# SV601272A-DAC.net
KiCad netlist of a schematic drawn in Altium Designer
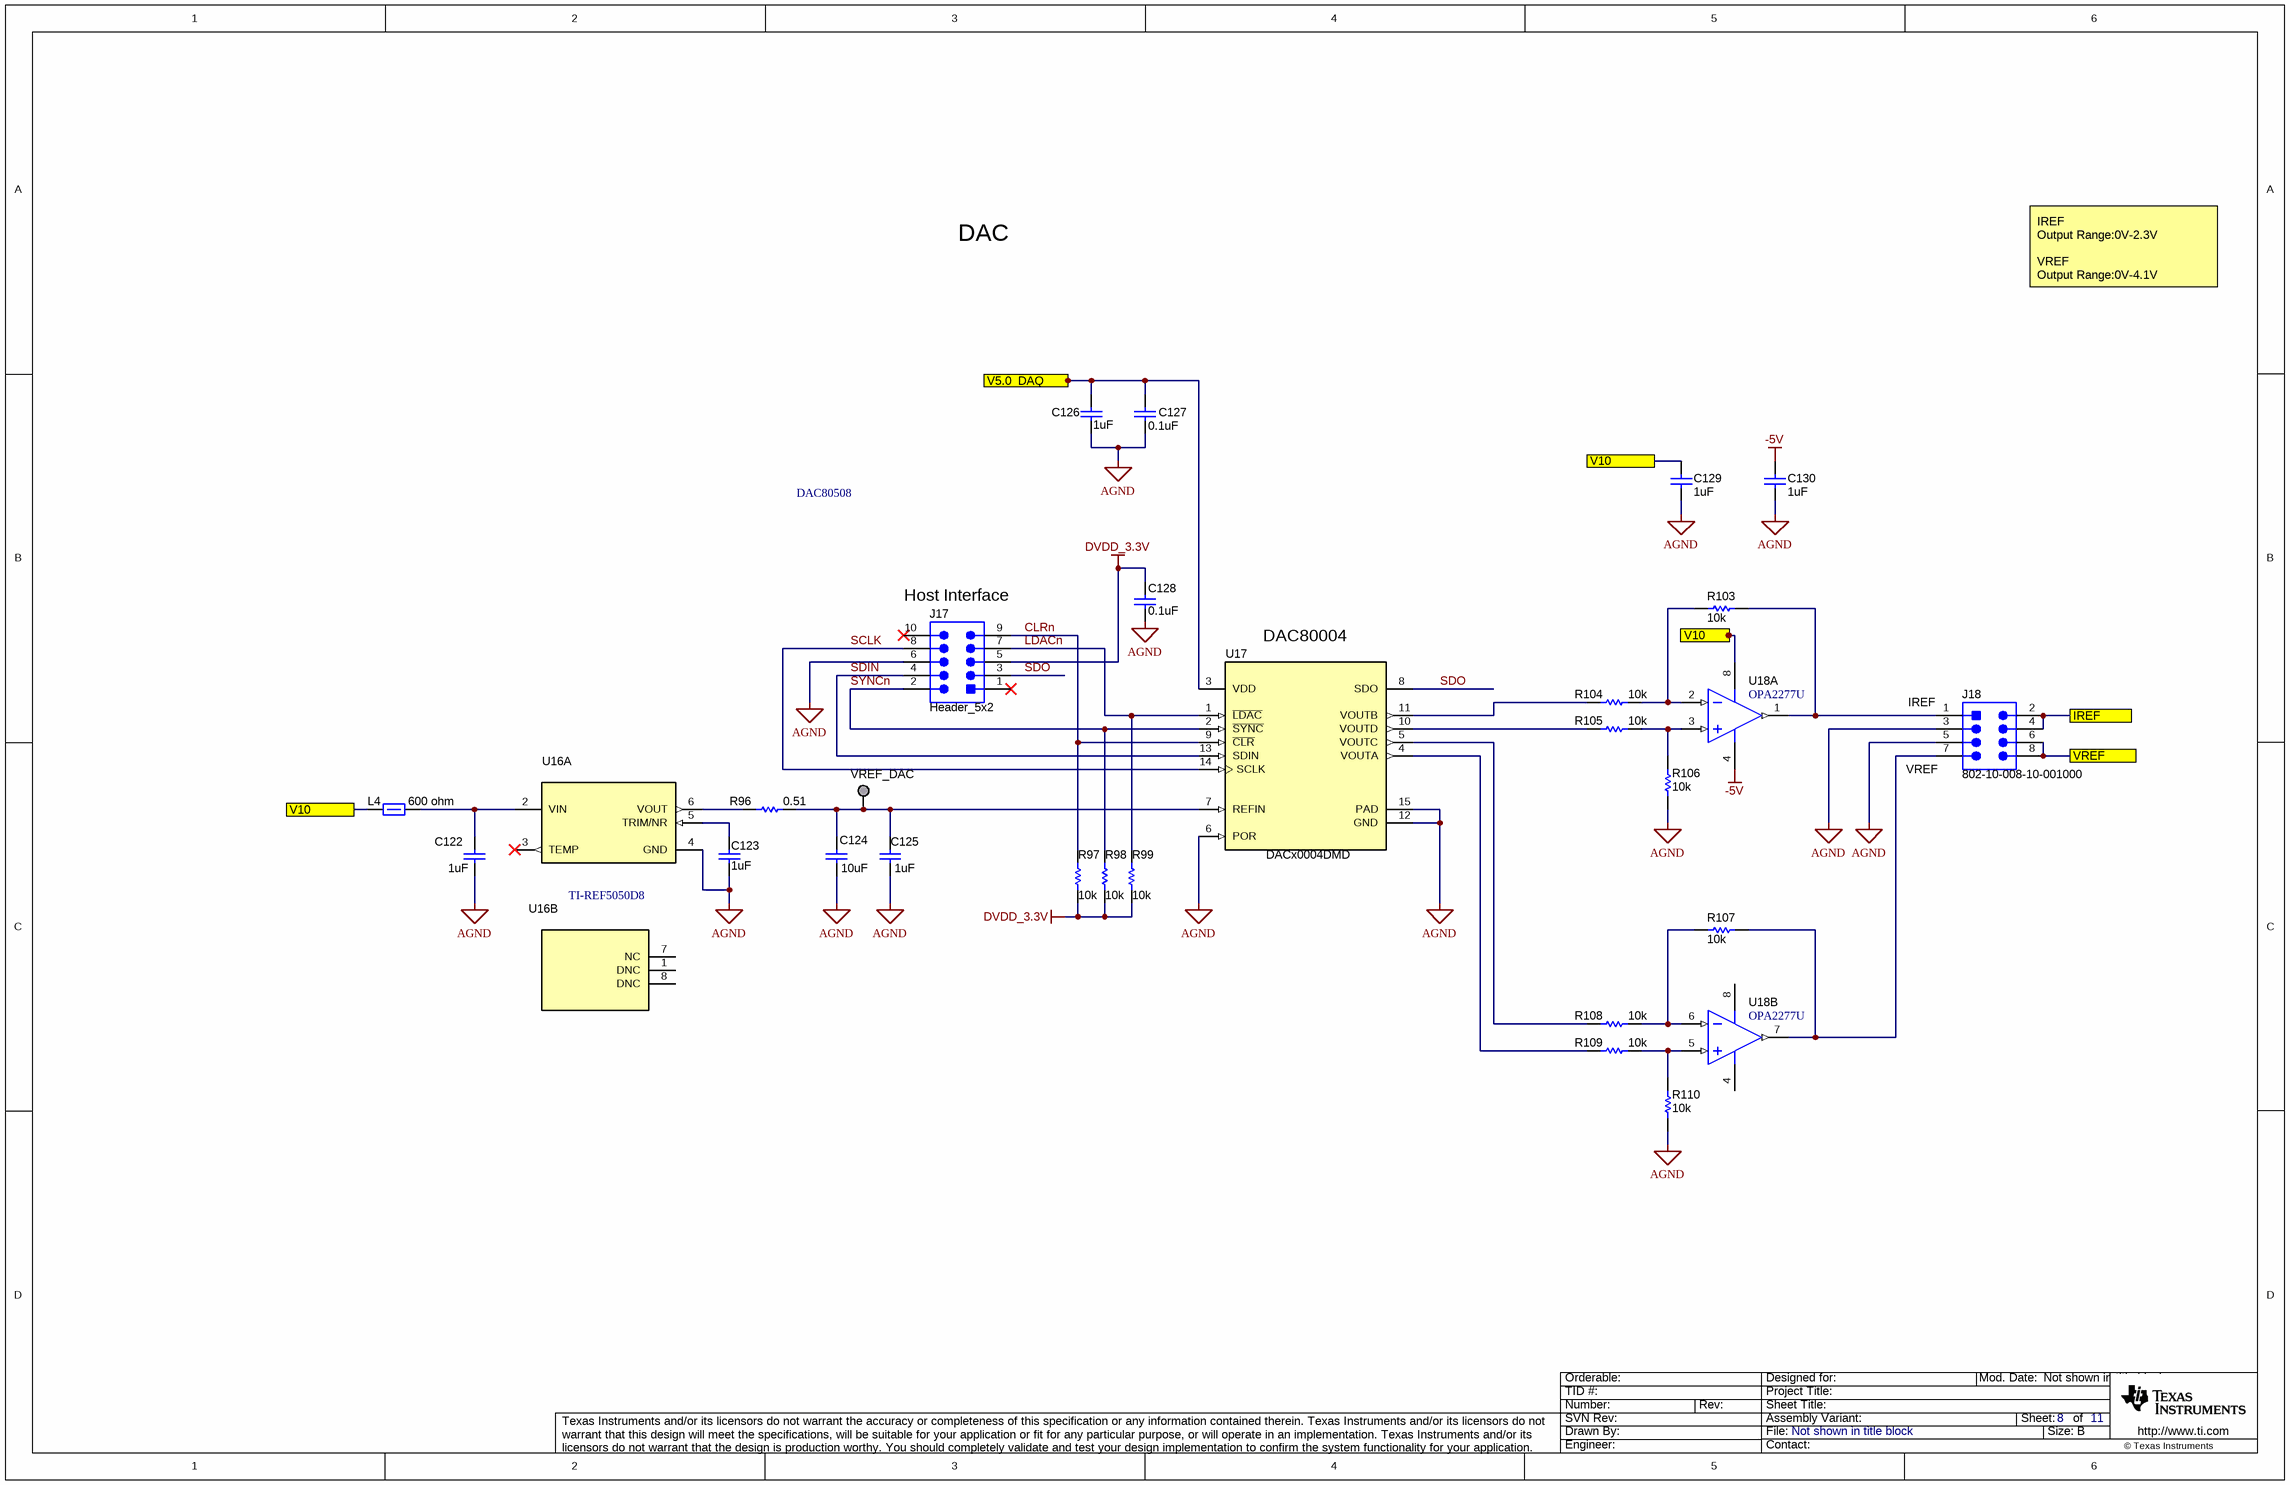
[diagram p0: SV601272A-DAC.SchDoc]

(export (version "E")
  (design (tool "Eeschema 10.0.6"))
  (components
    (comp (ref "C122")
      (value "Capacitor")
      (footprint "1206")
      (description "CAP, CERM, 1 uF, 25 V, +/- 10%, X7R, 1206")
      (fields
        (field (name "PARTNUMBER") "12063C105KAT2A")
        (field (name "VALUEDISPLAYED") "1uF")
        (field (name "MANUFACTURER") "AVX")
        (field (name "PUBLISHER") "Texas Instruments")
      )
      (libsource (lib "Altium Vault - TI") (part "CMP-0008509-2"))
    )
    (comp (ref "C123")
      (value "Capacitor")
      (footprint "1206")
      (description "CAP, CERM, 1 uF, 25 V, +/- 10%, X7R, 1206")
      (fields
        (field (name "PARTNUMBER") "12063C105KAT2A")
        (field (name "VALUEDISPLAYED") "1uF")
        (field (name "MANUFACTURER") "AVX")
        (field (name "PUBLISHER") "Texas Instruments")
      )
      (libsource (lib "Altium Vault - TI") (part "CMP-0008509-2"))
    )
    (comp (ref "C124")
      (value "Capacitor")
      (footprint "0805_HV")
      (description "CAP, CERM, 10 uF, 35 V, +/- 10%, X6S, 0805")
      (fields
        (field (name "PARTNUMBER") "GRM21BC8YA106KE11L")
        (field (name "VALUEDISPLAYED") "10uF")
        (field (name "MANUFACTURER") "MuRata")
        (field (name "PUBLISHER") "Texas Instruments")
      )
      (libsource (lib "Altium Vault - TI") (part "CMP-0008273-1"))
    )
    (comp (ref "C125")
      (value "Capacitor")
      (footprint "1206")
      (description "CAP, CERM, 1 uF, 25 V, +/- 10%, X7R, 1206")
      (fields
        (field (name "PARTNUMBER") "12063C105KAT2A")
        (field (name "VALUEDISPLAYED") "1uF")
        (field (name "MANUFACTURER") "AVX")
        (field (name "PUBLISHER") "Texas Instruments")
      )
      (libsource (lib "Altium Vault - TI") (part "CMP-0008509-2"))
    )
    (comp (ref "C126")
      (value "Capacitor")
      (footprint "1206")
      (description "CAP, CERM, 1 uF, 25 V, +/- 10%, X7R, 1206")
      (fields
        (field (name "PARTNUMBER") "12063C105KAT2A")
        (field (name "VALUEDISPLAYED") "1uF")
        (field (name "MANUFACTURER") "AVX")
        (field (name "PUBLISHER") "Texas Instruments")
      )
      (libsource (lib "Altium Vault - TI") (part "CMP-0008509-2"))
    )
    (comp (ref "C127")
      (value "Capacitor")
      (footprint "0603")
      (description "CAP, CERM, 0.1 uF, 16 V, +/- 5%, X7R, 0603")
      (fields
        (field (name "PARTNUMBER") "C0603C104J4RACTU")
        (field (name "VALUEDISPLAYED") "0.1uF")
        (field (name "MANUFACTURER") "Kemet")
        (field (name "PUBLISHER") "Texas Instruments")
      )
      (libsource (lib "Altium Vault - TI") (part "CMP-0006857-4"))
    )
    (comp (ref "C128")
      (value "Capacitor")
      (footprint "0603")
      (description "CAP, CERM, 0.1 uF, 16 V, +/- 5%, X7R, 0603")
      (fields
        (field (name "PARTNUMBER") "C0603C104J4RACTU")
        (field (name "VALUEDISPLAYED") "0.1uF")
        (field (name "MANUFACTURER") "Kemet")
        (field (name "PUBLISHER") "Texas Instruments")
      )
      (libsource (lib "Altium Vault - TI") (part "CMP-0006857-4"))
    )
    (comp (ref "C129")
      (value "Capacitor")
      (footprint "0603")
      (description "CAP, CERM, 1 uF, 35 V, +/- 10%, X7R, AEC-Q200 Grade 1, 0603")
      (fields
        (field (name "PARTNUMBER") "CGA3E1X7R1V105K080AC")
        (field (name "VALUEDISPLAYED") "1uF")
        (field (name "MANUFACTURER") "TDK")
        (field (name "PUBLISHER") "Texas Instruments")
      )
      (libsource (lib "Altium Vault - TI") (part "CMP-0007067-4"))
    )
    (comp (ref "C130")
      (value "Capacitor")
      (footprint "0603")
      (description "CAP, CERM, 1 uF, 35 V, +/- 10%, X7R, AEC-Q200 Grade 1, 0603")
      (fields
        (field (name "PARTNUMBER") "CGA3E1X7R1V105K080AC")
        (field (name "VALUEDISPLAYED") "1uF")
        (field (name "MANUFACTURER") "TDK")
        (field (name "PUBLISHER") "Texas Instruments")
      )
      (libsource (lib "Altium Vault - TI") (part "CMP-0007067-4"))
    )
    (comp (ref "J17")
      (value "Header_5x2")
      (footprint "Assman_AWHW-10G-0x02-T")
      (description "Header(Shrouded), 2.54mm, 5x2, Gold, TH")
      (fields
        (field (name "PARTNUMBER") "AWHW-10G-0202-T")
        (field (name "MANUFACTURER") "Assman WSW")
        (field (name "PUBLISHER") "Texas Instruments")
      )
      (libsource (lib "Altium Vault - TI") (part "CMP-0075161-1"))
    )
    (comp (ref "J18")
      (value "802-10-008-10-001000")
      (footprint "Mill-Max_802-10-008-10-001000")
      (description "Header, 2.54 mm, 4x2, Gold, TH")
      (fields (field (name "MANUFACTURER") "Mill-Max") (field (name "PUBLISHER") "Texas Instruments"))
      (libsource (lib "Altium Vault - TI") (part "CMP-0055096-1"))
    )
    (comp (ref "L4")
      (value "600 ohm")
      (footprint "0603")
      (description "Ferrite Bead, 600 ohm @ 100 MHz, 1 A, 0603")
      (fields
        (field (name "PARTNUMBER") "742792651")
        (field (name "MANUFACTURER") "Wurth Elektronik")
        (field (name "PUBLISHER") "Texas Instruments")
      )
      (libsource (lib "Altium Vault - TI") (part "Ferrite_Bead"))
    )
    (comp (ref "R96")
      (value "Resistor")
      (footprint "0603")
      (description "RES, 0.51, 1%, 0.1 W, AEC-Q200 Grade 1, 0603")
      (fields
        (field (name "PARTNUMBER") "ERJ-3RQFR51V")
        (field (name "VALUEDISPLAYED") "0.51")
        (field (name "MANUFACTURER") "Panasonic")
        (field (name "PUBLISHER") "Texas Instruments")
      )
      (libsource (lib "Altium Vault - TI") (part "CMP-0022717-2"))
    )
    (comp (ref "R97")
      (value "Resistor")
      (footprint "0603")
      (description "RES, 10 k, 5%, 0.1 W, AEC-Q200 Grade 0, 0603")
      (fields
        (field (name "PARTNUMBER") "CRCW060310K0JNEA")
        (field (name "VALUEDISPLAYED") "10k")
        (field (name "MANUFACTURER") "Vishay-Dale")
      )
      (libsource (lib "Altium Vault - TI") (part "CMP-0025701-4"))
    )
    (comp (ref "R98")
      (value "Resistor")
      (footprint "0603")
      (description "RES, 10 k, 5%, 0.1 W, AEC-Q200 Grade 0, 0603")
      (fields
        (field (name "PARTNUMBER") "CRCW060310K0JNEA")
        (field (name "VALUEDISPLAYED") "10k")
        (field (name "MANUFACTURER") "Vishay-Dale")
      )
      (libsource (lib "Altium Vault - TI") (part "CMP-0025701-4"))
    )
    (comp (ref "R99")
      (value "Resistor")
      (footprint "0603")
      (description "RES, 10 k, 5%, 0.1 W, AEC-Q200 Grade 0, 0603")
      (fields
        (field (name "PARTNUMBER") "CRCW060310K0JNEA")
        (field (name "VALUEDISPLAYED") "10k")
        (field (name "MANUFACTURER") "Vishay-Dale")
      )
      (libsource (lib "Altium Vault - TI") (part "CMP-0025701-4"))
    )
    (comp (ref "R103")
      (value "Resistor")
      (footprint "0603")
      (description "RES, 10 k, 5%, 0.1 W, AEC-Q200 Grade 0, 0603")
      (fields
        (field (name "PARTNUMBER") "CRCW060310K0JNEA")
        (field (name "VALUEDISPLAYED") "10k")
        (field (name "MANUFACTURER") "Vishay-Dale")
      )
      (libsource (lib "Altium Vault - TI") (part "CMP-0025701-4"))
    )
    (comp (ref "R104")
      (value "Resistor")
      (footprint "0603")
      (description "RES, 10 k, 5%, 0.1 W, AEC-Q200 Grade 0, 0603")
      (fields
        (field (name "PARTNUMBER") "CRCW060310K0JNEA")
        (field (name "VALUEDISPLAYED") "10k")
        (field (name "MANUFACTURER") "Vishay-Dale")
      )
      (libsource (lib "Altium Vault - TI") (part "CMP-0025701-4"))
    )
    (comp (ref "R105")
      (value "Resistor")
      (footprint "0603")
      (description "RES, 10 k, 5%, 0.1 W, AEC-Q200 Grade 0, 0603")
      (fields
        (field (name "PARTNUMBER") "CRCW060310K0JNEA")
        (field (name "VALUEDISPLAYED") "10k")
        (field (name "MANUFACTURER") "Vishay-Dale")
      )
      (libsource (lib "Altium Vault - TI") (part "CMP-0025701-4"))
    )
    (comp (ref "R106")
      (value "Resistor")
      (footprint "0603")
      (description "RES, 10 k, 5%, 0.1 W, AEC-Q200 Grade 0, 0603")
      (fields
        (field (name "PARTNUMBER") "CRCW060310K0JNEA")
        (field (name "VALUEDISPLAYED") "10k")
        (field (name "MANUFACTURER") "Vishay-Dale")
      )
      (libsource (lib "Altium Vault - TI") (part "CMP-0025701-4"))
    )
    (comp (ref "R107")
      (value "Resistor")
      (footprint "0603")
      (description "RES, 10 k, 5%, 0.1 W, AEC-Q200 Grade 0, 0603")
      (fields
        (field (name "PARTNUMBER") "CRCW060310K0JNEA")
        (field (name "VALUEDISPLAYED") "10k")
        (field (name "MANUFACTURER") "Vishay-Dale")
      )
      (libsource (lib "Altium Vault - TI") (part "CMP-0025701-4"))
    )
    (comp (ref "R108")
      (value "Resistor")
      (footprint "0603")
      (description "RES, 10 k, 5%, 0.1 W, AEC-Q200 Grade 0, 0603")
      (fields
        (field (name "PARTNUMBER") "CRCW060310K0JNEA")
        (field (name "VALUEDISPLAYED") "10k")
        (field (name "MANUFACTURER") "Vishay-Dale")
      )
      (libsource (lib "Altium Vault - TI") (part "CMP-0025701-4"))
    )
    (comp (ref "R109")
      (value "Resistor")
      (footprint "0603")
      (description "RES, 10 k, 5%, 0.1 W, AEC-Q200 Grade 0, 0603")
      (fields
        (field (name "PARTNUMBER") "CRCW060310K0JNEA")
        (field (name "VALUEDISPLAYED") "10k")
        (field (name "MANUFACTURER") "Vishay-Dale")
      )
      (libsource (lib "Altium Vault - TI") (part "CMP-0025701-4"))
    )
    (comp (ref "R110")
      (value "Resistor")
      (footprint "0603")
      (description "RES, 10 k, 5%, 0.1 W, AEC-Q200 Grade 0, 0603")
      (fields
        (field (name "PARTNUMBER") "CRCW060310K0JNEA")
        (field (name "VALUEDISPLAYED") "10k")
        (field (name "MANUFACTURER") "Vishay-Dale")
      )
      (libsource (lib "Altium Vault - TI") (part "CMP-0025701-4"))
    )
    (comp (ref "U16")
      (value "TI-REF5050D8")
      (footprint "D0008A_N")
      (fields (field (name "PARTNUMBER") "REF5050AID") (field (name "MANUFACTURER") "Texas Instruments"))
      (libsource (lib "Altium Vault - TI") (part "CMP-0032617-1"))
    )
    (comp (ref "U17")
      (value "DACx0004DMD")
      (footprint "DMD0014A")
      (description "QUAD 16-BIT, 1LSB INL, BUFFERED, VOLTAGE-OUTPUT DIGITAL-to-ANALOG CONVERTERS, DMD0014A (VSON-14)")
      (fields
        (field (name "PARTNUMBER") "DAC80004IDMD")
        (field (name "MANUFACTURER") "Texas Instruments")
        (field (name "PUBLISHER") "Texas Instruments")
      )
      (libsource (lib "Altium Vault - TI") (part "DACx0004DMD"))
    )
    (comp (ref "U18")
      (value "OPA2277U")
      (footprint "D0008A_N")
      (fields (field (name "MANUFACTURER") "Texas Instruments"))
      (libsource (lib "Altium Vault - TI") (part "CMP-0040655-1"))
    )
    (comp (ref "VREF_DAC")
      (value "Pogo Pad")
      (footprint "PogoPad")
      (description "Pad for Pogo Pin Connector")
      (fields (field (name "SYMBOLCREATOR") "codlsc") (field (name "PUBLISHER") "Texas Instruments"))
      (libsource (lib "MiscParts") (part "PogoPad"))
    )
  )
  (nets
    (net (code "1") (name "-5V") (class "Default")
      (node (ref "C130") (pin "1") (pinfunction "1_1") (pintype "passive"))
      (node (ref "U18") (pin "4") (pinfunction "V-_4") (pintype "power_in"))
    )
    (net (code "2") (name "/CLRn") (class "Default")
      (node (ref "J17") (pin "9") (pinfunction "9_9") (pintype "passive"))
      (node (ref "R97") (pin "2") (pinfunction "2_2") (pintype "passive"))
      (node (ref "U17") (pin "9") (pinfunction "CLR_9") (pintype "input"))
    )
    (net (code "3") (name "/IREF") (class "Default")
      (node (ref "J18") (pin "2") (pinfunction "2_2") (pintype "passive"))
      (node (ref "J18") (pin "4") (pinfunction "4_4") (pintype "passive"))
    )
    (net (code "4") (name "/LDACn") (class "Default")
      (node (ref "J17") (pin "7") (pinfunction "7_7") (pintype "passive"))
      (node (ref "R99") (pin "2") (pinfunction "2_2") (pintype "passive"))
      (node (ref "U17") (pin "1") (pinfunction "LDAC_1") (pintype "input"))
    )
    (net (code "5") (name "/SCLK") (class "Default")
      (node (ref "J17") (pin "8") (pinfunction "8_8") (pintype "passive"))
      (node (ref "U17") (pin "14") (pinfunction "SCLK_14") (pintype "input"))
    )
    (net (code "6") (name "/SDIN") (class "Default")
      (node (ref "J17") (pin "4") (pinfunction "4_4") (pintype "passive"))
      (node (ref "U17") (pin "13") (pinfunction "SDIN_13") (pintype "input"))
    )
    (net (code "7") (name "/SDO") (class "Default")
      (node (ref "J17") (pin "3") (pinfunction "3_3") (pintype "passive"))
      (node (ref "U17") (pin "8") (pinfunction "SDO_8") (pintype "tri_state"))
    )
    (net (code "8") (name "/SYNCn") (class "Default")
      (node (ref "J17") (pin "2") (pinfunction "2_2") (pintype "passive"))
      (node (ref "R98") (pin "2") (pinfunction "2_2") (pintype "passive"))
      (node (ref "U17") (pin "2") (pinfunction "SYNC_2") (pintype "input"))
    )
    (net (code "9") (name "/V5.0_DAQ") (class "Default")
      (node (ref "C126") (pin "1") (pinfunction "1_1") (pintype "passive"))
      (node (ref "C127") (pin "1") (pinfunction "1_1") (pintype "passive"))
      (node (ref "U17") (pin "3") (pinfunction "VDD_3") (pintype "power_in"))
    )
    (net (code "10") (name "/V10") (class "Default")
      (node (ref "C129") (pin "1") (pinfunction "1_1") (pintype "passive"))
      (node (ref "L4") (pin "1") (pinfunction "1_1") (pintype "passive"))
      (node (ref "U18") (pin "8") (pinfunction "V+_8") (pintype "power_in"))
    )
    (net (code "11") (name "/VREF") (class "Default")
      (node (ref "J18") (pin "6") (pinfunction "6_6") (pintype "passive"))
      (node (ref "J18") (pin "8") (pinfunction "8_8") (pintype "passive"))
    )
    (net (code "12") (name "AGND") (class "Default")
      (node (ref "C122") (pin "2") (pinfunction "2_2") (pintype "passive"))
      (node (ref "C123") (pin "2") (pinfunction "2_2") (pintype "passive"))
      (node (ref "C124") (pin "2") (pinfunction "2_2") (pintype "passive"))
      (node (ref "C125") (pin "2") (pinfunction "2_2") (pintype "passive"))
      (node (ref "C126") (pin "2") (pinfunction "2_2") (pintype "passive"))
      (node (ref "C127") (pin "2") (pinfunction "2_2") (pintype "passive"))
      (node (ref "C128") (pin "2") (pinfunction "2_2") (pintype "passive"))
      (node (ref "C129") (pin "2") (pinfunction "2_2") (pintype "passive"))
      (node (ref "C130") (pin "2") (pinfunction "2_2") (pintype "passive"))
      (node (ref "J17") (pin "6") (pinfunction "6_6") (pintype "passive"))
      (node (ref "J18") (pin "3") (pinfunction "3_3") (pintype "passive"))
      (node (ref "J18") (pin "5") (pinfunction "5_5") (pintype "passive"))
      (node (ref "R106") (pin "1") (pinfunction "1_1") (pintype "passive"))
      (node (ref "R110") (pin "1") (pinfunction "1_1") (pintype "passive"))
      (node (ref "U16") (pin "4") (pinfunction "GND_4") (pintype "power_in"))
      (node (ref "U17") (pin "12") (pinfunction "GND_12") (pintype "power_in"))
      (node (ref "U17") (pin "15") (pinfunction "PAD_15") (pintype "passive"))
      (node (ref "U17") (pin "6") (pinfunction "POR_6") (pintype "input"))
    )
    (net (code "13") (name "DVDD_3.3V") (class "Default")
      (node (ref "C128") (pin "1") (pinfunction "1_1") (pintype "passive"))
      (node (ref "J17") (pin "5") (pinfunction "5_5") (pintype "passive"))
      (node (ref "R97") (pin "1") (pinfunction "1_1") (pintype "passive"))
      (node (ref "R98") (pin "1") (pinfunction "1_1") (pintype "passive"))
      (node (ref "R99") (pin "1") (pinfunction "1_1") (pintype "passive"))
    )
    (net (code "14") (name "Net-(U16A-TRIM{slash}NR)") (class "Default")
      (node (ref "C123") (pin "1") (pinfunction "1_1") (pintype "passive"))
      (node (ref "U16") (pin "5") (pinfunction "TRIM/NR_5") (pintype "input"))
    )
    (net (code "15") (name "Net-(U16A-VIN)") (class "Default")
      (node (ref "C122") (pin "1") (pinfunction "1_1") (pintype "passive"))
      (node (ref "L4") (pin "2") (pinfunction "2_2") (pintype "passive"))
      (node (ref "U16") (pin "2") (pinfunction "VIN_2") (pintype "power_in"))
    )
    (net (code "16") (name "Net-(U16A-VOUT)") (class "Default")
      (node (ref "R96") (pin "1") (pinfunction "1_1") (pintype "passive"))
      (node (ref "U16") (pin "6") (pinfunction "VOUT_6") (pintype "output"))
    )
    (net (code "17") (name "Net-(U17-REFIN)") (class "Default")
      (node (ref "C124") (pin "1") (pinfunction "1_1") (pintype "passive"))
      (node (ref "C125") (pin "1") (pinfunction "1_1") (pintype "passive"))
      (node (ref "R96") (pin "2") (pinfunction "2_2") (pintype "passive"))
      (node (ref "U17") (pin "7") (pinfunction "REFIN_7") (pintype "input"))
      (node (ref "VREF_DAC") (pin "1") (pintype "passive"))
    )
    (net (code "18") (name "Net-(U17-VOUTA)") (class "Default")
      (node (ref "R109") (pin "2") (pinfunction "2_2") (pintype "passive"))
      (node (ref "U17") (pin "4") (pinfunction "VOUTA_4") (pintype "output"))
    )
    (net (code "19") (name "Net-(U17-VOUTB)") (class "Default")
      (node (ref "R104") (pin "2") (pinfunction "2_2") (pintype "passive"))
      (node (ref "U17") (pin "11") (pinfunction "VOUTB_11") (pintype "output"))
    )
    (net (code "20") (name "Net-(U17-VOUTC)") (class "Default")
      (node (ref "R108") (pin "2") (pinfunction "2_2") (pintype "passive"))
      (node (ref "U17") (pin "5") (pinfunction "VOUTC_5") (pintype "output"))
    )
    (net (code "21") (name "Net-(U17-VOUTD)") (class "Default")
      (node (ref "R105") (pin "2") (pinfunction "2_2") (pintype "passive"))
      (node (ref "U17") (pin "10") (pinfunction "VOUTD_10") (pintype "output"))
    )
    (net (code "22") (name "Net-(U18A-IN_A+)") (class "Default")
      (node (ref "R105") (pin "1") (pinfunction "1_1") (pintype "passive"))
      (node (ref "R106") (pin "2") (pinfunction "2_2") (pintype "passive"))
      (node (ref "U18") (pin "3") (pinfunction "IN_A+_3") (pintype "input"))
    )
    (net (code "23") (name "Net-(U18A-IN_A-)") (class "Default")
      (node (ref "R103") (pin "2") (pinfunction "2_2") (pintype "passive"))
      (node (ref "R104") (pin "1") (pinfunction "1_1") (pintype "passive"))
      (node (ref "U18") (pin "2") (pinfunction "IN_A-_2") (pintype "input"))
    )
    (net (code "24") (name "Net-(U18A-OUT_A)") (class "Default")
      (node (ref "J18") (pin "1") (pinfunction "1_1") (pintype "passive"))
      (node (ref "R103") (pin "1") (pinfunction "1_1") (pintype "passive"))
      (node (ref "U18") (pin "1") (pinfunction "OUT_A_1") (pintype "output"))
    )
    (net (code "25") (name "Net-(U18B-IN_B+)") (class "Default")
      (node (ref "R109") (pin "1") (pinfunction "1_1") (pintype "passive"))
      (node (ref "R110") (pin "2") (pinfunction "2_2") (pintype "passive"))
      (node (ref "U18") (pin "5") (pinfunction "IN_B+_5") (pintype "input"))
    )
    (net (code "26") (name "Net-(U18B-IN_B-)") (class "Default")
      (node (ref "R107") (pin "2") (pinfunction "2_2") (pintype "passive"))
      (node (ref "R108") (pin "1") (pinfunction "1_1") (pintype "passive"))
      (node (ref "U18") (pin "6") (pinfunction "IN_B-_6") (pintype "input"))
    )
    (net (code "27") (name "Net-(U18B-OUT_B)") (class "Default")
      (node (ref "J18") (pin "7") (pinfunction "7_7") (pintype "passive"))
      (node (ref "R107") (pin "1") (pinfunction "1_1") (pintype "passive"))
      (node (ref "U18") (pin "7") (pinfunction "OUT_B_7") (pintype "output"))
    )
    (net (code "28") (name "unconnected-(J17-Pad1)") (class "Default")
      (node (ref "J17") (pin "1") (pinfunction "1_1") (pintype "passive+no_connect"))
    )
    (net (code "29") (name "unconnected-(J17-Pad10)") (class "Default")
      (node (ref "J17") (pin "10") (pinfunction "10_10") (pintype "passive+no_connect"))
    )
    (net (code "30") (name "unconnected-(U16A-TEMP-Pad3)") (class "Default")
      (node (ref "U16") (pin "3") (pinfunction "TEMP_3") (pintype "output+no_connect"))
    )
    (net (code "31") (name "unconnected-(U16B-DNC-Pad1)") (class "Default")
      (node (ref "U16") (pin "1") (pinfunction "DNC_1") (pintype "passive"))
    )
    (net (code "32") (name "unconnected-(U16B-DNC-Pad8)") (class "Default")
      (node (ref "U16") (pin "8") (pinfunction "DNC_8") (pintype "passive"))
    )
    (net (code "33") (name "unconnected-(U16B-NC-Pad7)") (class "Default")
      (node (ref "U16") (pin "7") (pinfunction "NC_7") (pintype "passive"))
    )
    (net (code "34") (name "unconnected-(U18B-V+-Pad8)") (class "Default")
      (node (ref "U18") (pin "8") (pinfunction "V+_8") (pintype "power_in"))
    )
    (net (code "35") (name "unconnected-(U18B-V--Pad4)") (class "Default")
      (node (ref "U18") (pin "4") (pinfunction "V-_4") (pintype "power_in"))
    )
  )
)
